# bubble_sizer_sensor.net
KiCad netlist of a schematic drawn in EAGLE
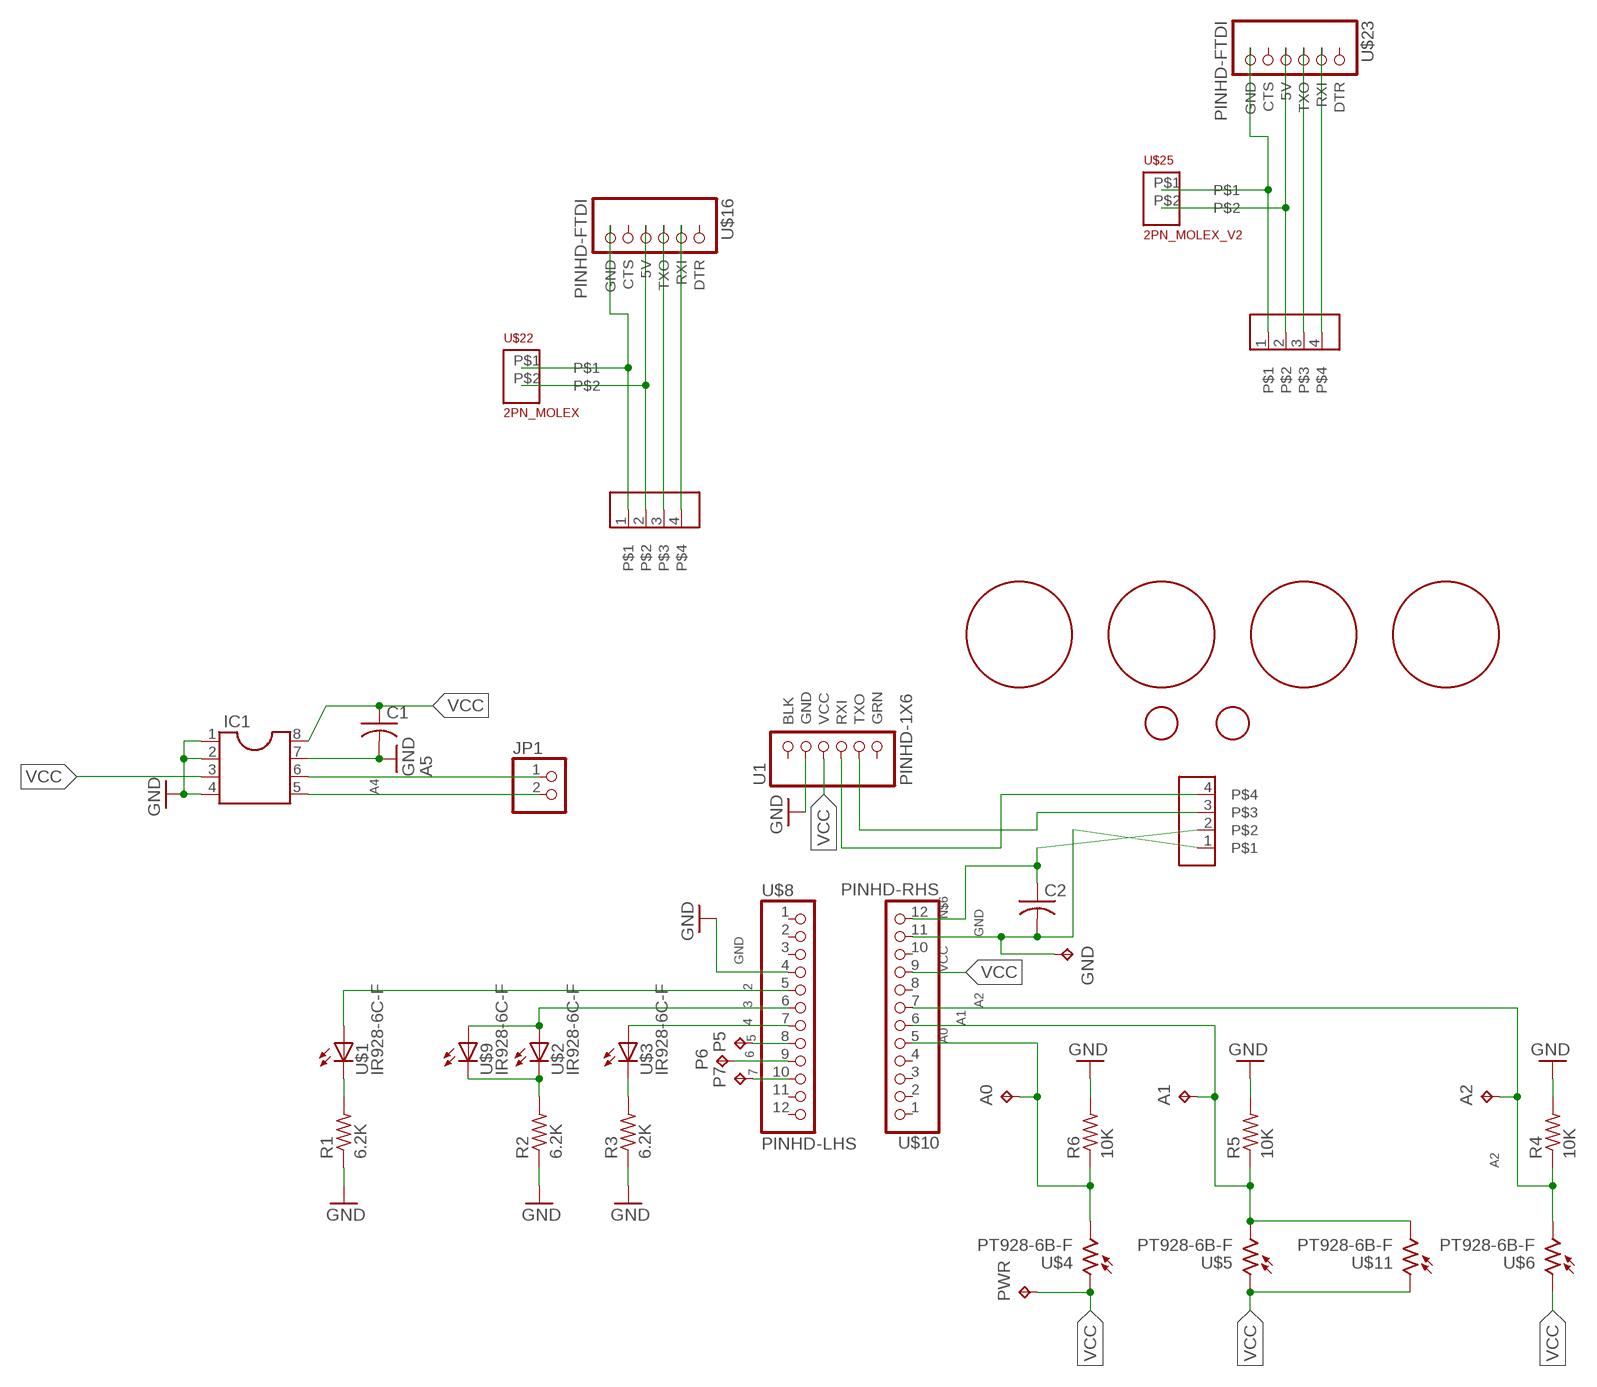
[diagram p0: schematic, sheet 1]

(export (version "E")
  (design (tool "Eeschema 10.0.6"))
  (components
    (comp (ref "A0")
      (value "TPPAD1-13")
      (footprint "eagle-import:P1-13")
      (libsource (lib "eagle-import") (part "TPPAD1-13"))
    )
    (comp (ref "A1")
      (value "TPPAD1-13")
      (footprint "eagle-import:P1-13")
      (libsource (lib "eagle-import") (part "TPPAD1-13"))
    )
    (comp (ref "A2")
      (value "TPPAD1-13")
      (footprint "eagle-import:P1-13")
      (libsource (lib "eagle-import") (part "TPPAD1-13"))
    )
    (comp (ref "C1")
      (value "C-USC0603")
      (footprint "eagle-import:C0603")
      (libsource (lib "eagle-import") (part "C-USC0603"))
    )
    (comp (ref "C2")
      (value "C-USC1210")
      (footprint "eagle-import:C1210")
      (libsource (lib "eagle-import") (part "C-USC1210"))
    )
    (comp (ref "GND")
      (value "TPPAD1-13")
      (footprint "eagle-import:P1-13")
      (libsource (lib "eagle-import") (part "TPPAD1-13"))
    )
    (comp (ref "IC1")
      (value "DIL8")
      (footprint "eagle-import:DIL08")
      (libsource (lib "eagle-import") (part "DIL8"))
    )
    (comp (ref "JP1")
      (value "PINHD-1X2")
      (footprint "eagle-import:1X02")
      (libsource (lib "eagle-import") (part "PINHD-1X2"))
    )
    (comp (ref "P5")
      (value "TPPAD1-13")
      (footprint "eagle-import:P1-13")
      (libsource (lib "eagle-import") (part "TPPAD1-13"))
    )
    (comp (ref "P6")
      (value "TPPAD1-13")
      (footprint "eagle-import:P1-13")
      (libsource (lib "eagle-import") (part "TPPAD1-13"))
    )
    (comp (ref "P7")
      (value "TPPAD1-13")
      (footprint "eagle-import:P1-13")
      (libsource (lib "eagle-import") (part "TPPAD1-13"))
    )
    (comp (ref "PWR")
      (value "TPPAD1-13")
      (footprint "eagle-import:P1-13")
      (libsource (lib "eagle-import") (part "TPPAD1-13"))
    )
    (comp (ref "R1")
      (value "6.2K")
      (footprint "eagle-import:R0603")
      (libsource (lib "eagle-import") (part "R-US_R0603"))
    )
    (comp (ref "R2")
      (value "6.2K")
      (footprint "eagle-import:R0603")
      (libsource (lib "eagle-import") (part "R-US_R0603"))
    )
    (comp (ref "R3")
      (value "6.2K")
      (footprint "eagle-import:R0603")
      (libsource (lib "eagle-import") (part "R-US_R0603"))
    )
    (comp (ref "R4")
      (value "10K")
      (footprint "eagle-import:R0603")
      (libsource (lib "eagle-import") (part "R-US_R0603"))
    )
    (comp (ref "R5")
      (value "10K")
      (footprint "eagle-import:R0603")
      (libsource (lib "eagle-import") (part "R-US_R0603"))
    )
    (comp (ref "R6")
      (value "10K")
      (footprint "eagle-import:R0603")
      (libsource (lib "eagle-import") (part "R-US_R0603"))
    )
    (comp (ref "U$1")
      (value "IR928-6C-F")
      (footprint "eagle-import:LED_LAYOUT")
      (libsource (lib "eagle-import") (part "IR928-6C-F"))
    )
    (comp (ref "U$2")
      (value "IR928-6C-F")
      (footprint "eagle-import:LED_LAYOUT")
      (libsource (lib "eagle-import") (part "IR928-6C-F"))
    )
    (comp (ref "U$3")
      (value "IR928-6C-F")
      (footprint "eagle-import:LED_LAYOUT")
      (libsource (lib "eagle-import") (part "IR928-6C-F"))
    )
    (comp (ref "U$4")
      (value "PT928-6B-F")
      (footprint "eagle-import:LED_LAYOUT")
      (libsource (lib "eagle-import") (part "PT928-6B-F"))
    )
    (comp (ref "U$5")
      (value "PT928-6B-F")
      (footprint "eagle-import:LED_LAYOUT")
      (libsource (lib "eagle-import") (part "PT928-6B-F"))
    )
    (comp (ref "U$6")
      (value "PT928-6B-F")
      (footprint "eagle-import:LED_LAYOUT")
      (libsource (lib "eagle-import") (part "PT928-6B-F"))
    )
    (comp (ref "U$8")
      (value "PINHD-LHS")
      (footprint "eagle-import:1X12")
      (libsource (lib "eagle-import") (part "PINHD-LHS"))
    )
    (comp (ref "U$9")
      (value "IR928-6C-F")
      (footprint "eagle-import:LED_LAYOUT")
      (libsource (lib "eagle-import") (part "IR928-6C-F"))
    )
    (comp (ref "U$10")
      (value "PINHD-RHS")
      (footprint "eagle-import:1X12")
      (libsource (lib "eagle-import") (part "PINHD-RHS"))
    )
    (comp (ref "U$11")
      (value "PT928-6B-F")
      (footprint "eagle-import:LED_LAYOUT")
      (libsource (lib "eagle-import") (part "PT928-6B-F"))
    )
    (comp (ref "U$13")
      (value "M2_SCREW_HOLE")
      (footprint "eagle-import:M2_SCREW_HOLE")
      (libsource (lib "eagle-import") (part "M2_SCREW_HOLE"))
    )
    (comp (ref "U$14")
      (value "MICROFIT3.0_4POS_SMD")
      (footprint "eagle-import:MICRO_FIT3.0_4POS-SM")
      (libsource (lib "eagle-import") (part "MICROFIT3.0_4POS_SMD"))
    )
    (comp (ref "U$15")
      (value "M2_SCREW_HOLE")
      (footprint "eagle-import:M2_SCREW_HOLE")
      (libsource (lib "eagle-import") (part "M2_SCREW_HOLE"))
    )
    (comp (ref "U$16")
      (value "PINHD-FTDI")
      (footprint "eagle-import:1X6")
      (libsource (lib "eagle-import") (part "PINHD-FTDI"))
    )
    (comp (ref "U$17")
      (value "UBOLT_HOLE")
      (footprint "eagle-import:UBOLT_HOLE")
      (libsource (lib "eagle-import") (part "UBOLT_HOLE"))
    )
    (comp (ref "U$18")
      (value "UBOLT_HOLE")
      (footprint "eagle-import:UBOLT_HOLE")
      (libsource (lib "eagle-import") (part "UBOLT_HOLE"))
    )
    (comp (ref "U$19")
      (value "UBOLT_HOLE")
      (footprint "eagle-import:UBOLT_HOLE")
      (libsource (lib "eagle-import") (part "UBOLT_HOLE"))
    )
    (comp (ref "U$20")
      (value "UBOLT_HOLE")
      (footprint "eagle-import:UBOLT_HOLE")
      (libsource (lib "eagle-import") (part "UBOLT_HOLE"))
    )
    (comp (ref "U$21")
      (value "MICROFIT3.0_4POS_SMD")
      (footprint "eagle-import:MICRO_FIT3.0_4POS-SM")
      (libsource (lib "eagle-import") (part "MICROFIT3.0_4POS_SMD"))
    )
    (comp (ref "U$22")
      (value "2PN_MOLEX")
      (footprint "eagle-import:2PN_MOLEX")
      (libsource (lib "eagle-import") (part "2PN_MOLEX"))
    )
    (comp (ref "U$23")
      (value "PINHD-FTDI")
      (footprint "eagle-import:1X6")
      (libsource (lib "eagle-import") (part "PINHD-FTDI"))
    )
    (comp (ref "U$24")
      (value "MICROFIT3.0_4POS_SMD")
      (footprint "eagle-import:MICRO_FIT3.0_4POS-SM")
      (libsource (lib "eagle-import") (part "MICROFIT3.0_4POS_SMD"))
    )
    (comp (ref "U$25")
      (value "2PN_MOLEX_V2")
      (footprint "eagle-import:2PN_MOLEX_V2")
      (libsource (lib "eagle-import") (part "2PN_MOLEX_V2"))
    )
    (comp (ref "U1")
      (value "PINHD-1X6")
      (footprint "eagle-import:1X6")
      (libsource (lib "eagle-import") (part "PINHD-1X6"))
    )
  )
  (nets
    (net (code "1") (name "/2") (class "Default")
      (node (ref "U$1") (pin "PWR") (pinfunction "PWR_PWR") (pintype "passive"))
      (node (ref "U$8") (pin "5") (pinfunction "2_5") (pintype "passive"))
    )
    (net (code "2") (name "/3") (class "Default")
      (node (ref "U$2") (pin "PWR") (pinfunction "PWR_PWR") (pintype "passive"))
      (node (ref "U$8") (pin "6") (pinfunction "3_6") (pintype "passive"))
      (node (ref "U$9") (pin "PWR") (pinfunction "PWR_PWR") (pintype "passive"))
    )
    (net (code "3") (name "/4") (class "Default")
      (node (ref "U$3") (pin "PWR") (pinfunction "PWR_PWR") (pintype "passive"))
      (node (ref "U$8") (pin "7") (pinfunction "4_7") (pintype "passive"))
    )
    (net (code "4") (name "/5") (class "Default")
      (node (ref "P5") (pin "TP") (pinfunction "TP_TP") (pintype "input"))
      (node (ref "U$8") (pin "8") (pinfunction "5_8") (pintype "passive"))
    )
    (net (code "5") (name "/6") (class "Default")
      (node (ref "P6") (pin "TP") (pinfunction "TP_TP") (pintype "input"))
      (node (ref "U$8") (pin "9") (pinfunction "6_9") (pintype "passive"))
    )
    (net (code "6") (name "/7") (class "Default")
      (node (ref "P7") (pin "TP") (pinfunction "TP_TP") (pintype "input"))
      (node (ref "U$8") (pin "10") (pinfunction "7_10") (pintype "passive"))
    )
    (net (code "7") (name "/A0") (class "Default")
      (node (ref "A0") (pin "TP") (pinfunction "TP_TP") (pintype "input"))
      (node (ref "R6") (pin "1") (pinfunction "1_1") (pintype "passive"))
      (node (ref "U$10") (pin "5") (pinfunction "A3_5") (pintype "passive"))
      (node (ref "U$4") (pin "RSTR") (pinfunction "RSTR_RSTR") (pintype "passive"))
    )
    (net (code "8") (name "/A1") (class "Default")
      (node (ref "A1") (pin "TP") (pinfunction "TP_TP") (pintype "input"))
      (node (ref "R5") (pin "1") (pinfunction "1_1") (pintype "passive"))
      (node (ref "U$10") (pin "6") (pinfunction "A2_6") (pintype "passive"))
      (node (ref "U$11") (pin "RSTR") (pinfunction "RSTR_RSTR") (pintype "passive"))
      (node (ref "U$5") (pin "RSTR") (pinfunction "RSTR_RSTR") (pintype "passive"))
    )
    (net (code "9") (name "/A2") (class "Default")
      (node (ref "A2") (pin "TP") (pinfunction "TP_TP") (pintype "input"))
      (node (ref "R4") (pin "1") (pinfunction "1_1") (pintype "passive"))
      (node (ref "U$10") (pin "7") (pinfunction "A1_7") (pintype "passive"))
      (node (ref "U$6") (pin "RSTR") (pinfunction "RSTR_RSTR") (pintype "passive"))
    )
    (net (code "10") (name "/A4") (class "Default")
      (node (ref "IC1") (pin "5") (pinfunction "5_5") (pintype "passive"))
      (node (ref "JP1") (pin "2") (pinfunction "2_2") (pintype "passive"))
    )
    (net (code "11") (name "/A5") (class "Default")
      (node (ref "IC1") (pin "6") (pinfunction "6_6") (pintype "passive"))
      (node (ref "JP1") (pin "1") (pinfunction "1_1") (pintype "passive"))
    )
    (net (code "12") (name "/N$6") (class "Default")
      (node (ref "C2") (pin "1") (pinfunction "1_1") (pintype "passive"))
      (node (ref "U$10") (pin "12") (pinfunction "10_12") (pintype "passive"))
      (node (ref "U$14") (pin "2") (pinfunction "P$2_2") (pintype "bidirectional"))
    )
    (net (code "13") (name "GND") (class "Default")
      (node (ref "C1") (pin "2") (pinfunction "2_2") (pintype "passive"))
      (node (ref "C2") (pin "2") (pinfunction "2_2") (pintype "passive"))
      (node (ref "GND") (pin "TP") (pinfunction "TP_TP") (pintype "input"))
      (node (ref "IC1") (pin "1") (pinfunction "1_1") (pintype "passive"))
      (node (ref "IC1") (pin "2") (pinfunction "2_2") (pintype "passive"))
      (node (ref "IC1") (pin "4") (pinfunction "4_4") (pintype "passive"))
      (node (ref "IC1") (pin "7") (pinfunction "7_7") (pintype "passive"))
      (node (ref "R1") (pin "1") (pinfunction "1_1") (pintype "passive"))
      (node (ref "R2") (pin "1") (pinfunction "1_1") (pintype "passive"))
      (node (ref "R3") (pin "1") (pinfunction "1_1") (pintype "passive"))
      (node (ref "R4") (pin "2") (pinfunction "2_2") (pintype "passive"))
      (node (ref "R5") (pin "2") (pinfunction "2_2") (pintype "passive"))
      (node (ref "R6") (pin "2") (pinfunction "2_2") (pintype "passive"))
      (node (ref "U$10") (pin "11") (pinfunction "11_11") (pintype "passive"))
      (node (ref "U$14") (pin "1") (pinfunction "P$1_1") (pintype "bidirectional"))
      (node (ref "U$8") (pin "4") (pinfunction "GND_4") (pintype "passive"))
      (node (ref "U1") (pin "2") (pinfunction "GND_2") (pintype "bidirectional"))
    )
    (net (code "14") (name "Net-(R1-Pad2)") (class "Default")
      (node (ref "R1") (pin "2") (pinfunction "2_2") (pintype "passive"))
      (node (ref "U$1") (pin "RSTR") (pinfunction "RSTR_RSTR") (pintype "passive"))
    )
    (net (code "15") (name "Net-(R2-Pad2)") (class "Default")
      (node (ref "R2") (pin "2") (pinfunction "2_2") (pintype "passive"))
      (node (ref "U$2") (pin "RSTR") (pinfunction "RSTR_RSTR") (pintype "passive"))
      (node (ref "U$9") (pin "RSTR") (pinfunction "RSTR_RSTR") (pintype "passive"))
    )
    (net (code "16") (name "Net-(R3-Pad2)") (class "Default")
      (node (ref "R3") (pin "2") (pinfunction "2_2") (pintype "passive"))
      (node (ref "U$3") (pin "RSTR") (pinfunction "RSTR_RSTR") (pintype "passive"))
    )
    (net (code "17") (name "Net-(U$14-P$3)") (class "Default")
      (node (ref "U$14") (pin "3") (pinfunction "P$3_3") (pintype "bidirectional"))
      (node (ref "U1") (pin "5") (pinfunction "TXO_5") (pintype "bidirectional"))
    )
    (net (code "18") (name "Net-(U$14-P$4)") (class "Default")
      (node (ref "U$14") (pin "4") (pinfunction "P$4_4") (pintype "bidirectional"))
      (node (ref "U1") (pin "4") (pinfunction "RXI_4") (pintype "bidirectional"))
    )
    (net (code "19") (name "Net-(U$16-5V)") (class "Default")
      (node (ref "U$16") (pin "4") (pinfunction "5V_4") (pintype "bidirectional"))
      (node (ref "U$21") (pin "2") (pinfunction "P$2_2") (pintype "bidirectional"))
      (node (ref "U$22") (pin "P$2") (pinfunction "P$2_P$2") (pintype "bidirectional"))
    )
    (net (code "20") (name "Net-(U$16-GND)") (class "Default")
      (node (ref "U$16") (pin "6") (pinfunction "GND_6") (pintype "bidirectional"))
      (node (ref "U$21") (pin "1") (pinfunction "P$1_1") (pintype "bidirectional"))
      (node (ref "U$22") (pin "P$1") (pinfunction "P$1_P$1") (pintype "bidirectional"))
    )
    (net (code "21") (name "Net-(U$16-RXI)") (class "Default")
      (node (ref "U$16") (pin "2") (pinfunction "RXI_2") (pintype "bidirectional"))
      (node (ref "U$21") (pin "4") (pinfunction "P$4_4") (pintype "bidirectional"))
    )
    (net (code "22") (name "Net-(U$16-TXO)") (class "Default")
      (node (ref "U$16") (pin "3") (pinfunction "TXO_3") (pintype "bidirectional"))
      (node (ref "U$21") (pin "3") (pinfunction "P$3_3") (pintype "bidirectional"))
    )
    (net (code "23") (name "Net-(U$23-5V)") (class "Default")
      (node (ref "U$23") (pin "4") (pinfunction "5V_4") (pintype "bidirectional"))
      (node (ref "U$24") (pin "2") (pinfunction "P$2_2") (pintype "bidirectional"))
      (node (ref "U$25") (pin "P$2") (pinfunction "P$2_P$2") (pintype "bidirectional"))
    )
    (net (code "24") (name "Net-(U$23-GND)") (class "Default")
      (node (ref "U$23") (pin "6") (pinfunction "GND_6") (pintype "bidirectional"))
      (node (ref "U$24") (pin "1") (pinfunction "P$1_1") (pintype "bidirectional"))
      (node (ref "U$25") (pin "P$1") (pinfunction "P$1_P$1") (pintype "bidirectional"))
    )
    (net (code "25") (name "Net-(U$23-RXI)") (class "Default")
      (node (ref "U$23") (pin "2") (pinfunction "RXI_2") (pintype "bidirectional"))
      (node (ref "U$24") (pin "4") (pinfunction "P$4_4") (pintype "bidirectional"))
    )
    (net (code "26") (name "Net-(U$23-TXO)") (class "Default")
      (node (ref "U$23") (pin "3") (pinfunction "TXO_3") (pintype "bidirectional"))
      (node (ref "U$24") (pin "3") (pinfunction "P$3_3") (pintype "bidirectional"))
    )
    (net (code "27") (name "VCC") (class "Default")
      (node (ref "C1") (pin "1") (pinfunction "1_1") (pintype "passive"))
      (node (ref "IC1") (pin "3") (pinfunction "3_3") (pintype "passive"))
      (node (ref "IC1") (pin "8") (pinfunction "8_8") (pintype "passive"))
      (node (ref "PWR") (pin "TP") (pinfunction "TP_TP") (pintype "input"))
      (node (ref "U$10") (pin "9") (pinfunction "13_9") (pintype "passive"))
      (node (ref "U$11") (pin "PWR") (pinfunction "PWR_PWR") (pintype "passive"))
      (node (ref "U$4") (pin "PWR") (pinfunction "PWR_PWR") (pintype "passive"))
      (node (ref "U$5") (pin "PWR") (pinfunction "PWR_PWR") (pintype "passive"))
      (node (ref "U$6") (pin "PWR") (pinfunction "PWR_PWR") (pintype "passive"))
      (node (ref "U1") (pin "3") (pinfunction "VCC_3") (pintype "bidirectional"))
    )
    (net (code "28") (name "unconnected-(U$8-8-Pad11)") (class "Default")
      (node (ref "U$8") (pin "11") (pinfunction "8_11") (pintype "passive"))
    )
    (net (code "29") (name "unconnected-(U$8-9-Pad12)") (class "Default")
      (node (ref "U$8") (pin "12") (pinfunction "9_12") (pintype "passive"))
    )
    (net (code "30") (name "unconnected-(U$8-RST-Pad3)") (class "Default")
      (node (ref "U$8") (pin "3") (pinfunction "RST_3") (pintype "passive"))
    )
    (net (code "31") (name "unconnected-(U$8-RXI-Pad2)") (class "Default")
      (node (ref "U$8") (pin "2") (pinfunction "RXI_2") (pintype "passive"))
    )
    (net (code "32") (name "unconnected-(U$8-TXO-Pad1)") (class "Default")
      (node (ref "U$8") (pin "1") (pinfunction "TXO_1") (pintype "passive"))
    )
    (net (code "33") (name "unconnected-(U$10-12-Pad10)") (class "Default")
      (node (ref "U$10") (pin "10") (pinfunction "12_10") (pintype "passive"))
    )
    (net (code "34") (name "unconnected-(U$10-A0-Pad8)") (class "Default")
      (node (ref "U$10") (pin "8") (pinfunction "A0_8") (pintype "passive"))
    )
    (net (code "35") (name "unconnected-(U$10-GND2-Pad2)") (class "Default")
      (node (ref "U$10") (pin "2") (pinfunction "GND2_2") (pintype "passive"))
    )
    (net (code "36") (name "unconnected-(U$10-RAW-Pad1)") (class "Default")
      (node (ref "U$10") (pin "1") (pinfunction "RAW_1") (pintype "passive"))
    )
    (net (code "37") (name "unconnected-(U$10-RST-Pad3)") (class "Default")
      (node (ref "U$10") (pin "3") (pinfunction "RST_3") (pintype "passive"))
    )
    (net (code "38") (name "unconnected-(U$10-VCC-Pad4)") (class "Default")
      (node (ref "U$10") (pin "4") (pinfunction "VCC_4") (pintype "passive"))
    )
    (net (code "39") (name "unconnected-(U$16-CTS-Pad5)") (class "Default")
      (node (ref "U$16") (pin "5") (pinfunction "CTS_5") (pintype "bidirectional"))
    )
    (net (code "40") (name "unconnected-(U$16-DTR-Pad1)") (class "Default")
      (node (ref "U$16") (pin "1") (pinfunction "DTR_1") (pintype "bidirectional"))
    )
    (net (code "41") (name "unconnected-(U$23-CTS-Pad5)") (class "Default")
      (node (ref "U$23") (pin "5") (pinfunction "CTS_5") (pintype "bidirectional"))
    )
    (net (code "42") (name "unconnected-(U$23-DTR-Pad1)") (class "Default")
      (node (ref "U$23") (pin "1") (pinfunction "DTR_1") (pintype "bidirectional"))
    )
    (net (code "43") (name "unconnected-(U1-BLK-Pad1)") (class "Default")
      (node (ref "U1") (pin "1") (pinfunction "BLK_1") (pintype "bidirectional"))
    )
    (net (code "44") (name "unconnected-(U1-GRN-Pad6)") (class "Default")
      (node (ref "U1") (pin "6") (pinfunction "GRN_6") (pintype "bidirectional"))
    )
  )
)
